# design.net
KiCad netlist of a schematic drawn in EAGLE
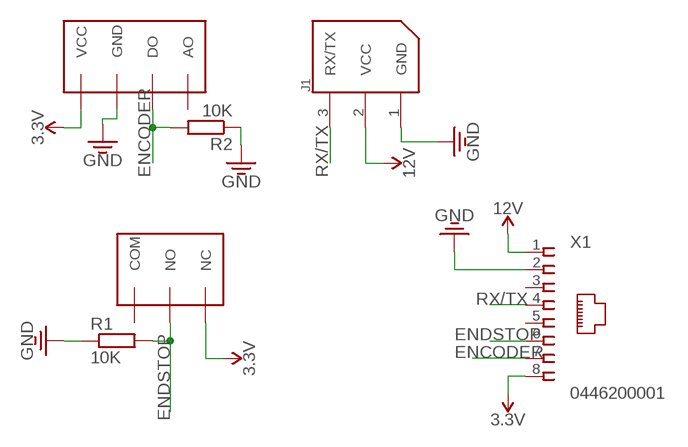
[diagram p0: schematic, sheet 1]

(export (version "E")
  (design (tool "Eeschema 10.0.6"))
  (components
    (comp (ref "J1")
      (value "22-03-5035")
      (footprint "eagle-import:5267-3")
      (libsource (lib "eagle-import") (part "22-03-5035"))
    )
    (comp (ref "R1")
      (value "10K")
      (footprint "eagle-import:0204_7")
      (libsource (lib "eagle-import") (part "R-EU_0204/7"))
    )
    (comp (ref "R2")
      (value "10K")
      (footprint "eagle-import:0204_7")
      (libsource (lib "eagle-import") (part "R-EU_0204/7"))
    )
    (comp (ref "U$1")
      (value "OPTICAL_ENCODER_FC-01")
      (footprint "eagle-import:OPTICAL_ENCODER_FC-01")
      (libsource (lib "eagle-import") (part "OPTICAL_ENCODER_FC-01"))
    )
    (comp (ref "U$2")
      (value "ENDSTOP")
      (footprint "eagle-import:ENDSTOP")
      (libsource (lib "eagle-import") (part "ENDSTOP"))
    )
    (comp (ref "X1")
      (value "0446200001")
      (footprint "eagle-import:0446200001")
      (fields (field (name "MF") "MOLEX"))
      (libsource (lib "eagle-import") (part "0446200001"))
    )
  )
  (nets
    (net (code "1") (name "/ENCODER") (class "Default")
      (node (ref "R2") (pin "2") (pinfunction "2_2") (pintype "passive"))
      (node (ref "U$1") (pin "DO") (pinfunction "DO_DO") (pintype "bidirectional"))
      (node (ref "X1") (pin "7") (pinfunction "7_7") (pintype "passive"))
    )
    (net (code "2") (name "/ENDSTOP") (class "Default")
      (node (ref "R1") (pin "2") (pinfunction "2_2") (pintype "passive"))
      (node (ref "U$2") (pin "NO") (pinfunction "NO_NO") (pintype "bidirectional"))
      (node (ref "X1") (pin "6") (pinfunction "6_6") (pintype "passive"))
    )
    (net (code "3") (name "/RX{slash}TX") (class "Default")
      (node (ref "J1") (pin "3") (pinfunction "RX/TX_3") (pintype "bidirectional"))
      (node (ref "X1") (pin "4") (pinfunction "4_4") (pintype "passive"))
    )
    (net (code "4") (name "3.3V") (class "Default")
      (node (ref "U$1") (pin "VCC") (pinfunction "VCC_VCC") (pintype "bidirectional"))
      (node (ref "U$2") (pin "NC") (pinfunction "NC_NC") (pintype "bidirectional"))
      (node (ref "X1") (pin "8") (pinfunction "8_8") (pintype "passive"))
    )
    (net (code "5") (name "12V") (class "Default")
      (node (ref "J1") (pin "2") (pinfunction "VCC_2") (pintype "bidirectional"))
      (node (ref "X1") (pin "1") (pinfunction "1_1") (pintype "passive"))
    )
    (net (code "6") (name "GND") (class "Default")
      (node (ref "J1") (pin "1") (pinfunction "GND_1") (pintype "bidirectional"))
      (node (ref "R1") (pin "1") (pinfunction "1_1") (pintype "passive"))
      (node (ref "R2") (pin "1") (pinfunction "1_1") (pintype "passive"))
      (node (ref "U$1") (pin "GND") (pinfunction "GND_GND") (pintype "bidirectional"))
      (node (ref "X1") (pin "2") (pinfunction "2_2") (pintype "passive"))
    )
    (net (code "7") (name "unconnected-(U$1-PadAO)") (class "Default")
      (node (ref "U$1") (pin "AO") (pinfunction "AO_AO") (pintype "bidirectional"))
    )
    (net (code "8") (name "unconnected-(U$2-PadCOM)") (class "Default")
      (node (ref "U$2") (pin "COM") (pinfunction "COM_COM") (pintype "bidirectional"))
    )
    (net (code "9") (name "unconnected-(X1-Pad3)") (class "Default")
      (node (ref "X1") (pin "3") (pinfunction "3_3") (pintype "passive"))
    )
    (net (code "10") (name "unconnected-(X1-Pad5)") (class "Default")
      (node (ref "X1") (pin "5") (pinfunction "5_5") (pintype "passive"))
    )
  )
)
